# Gyroscope.net
KiCad netlist of a schematic drawn in Altium Designer
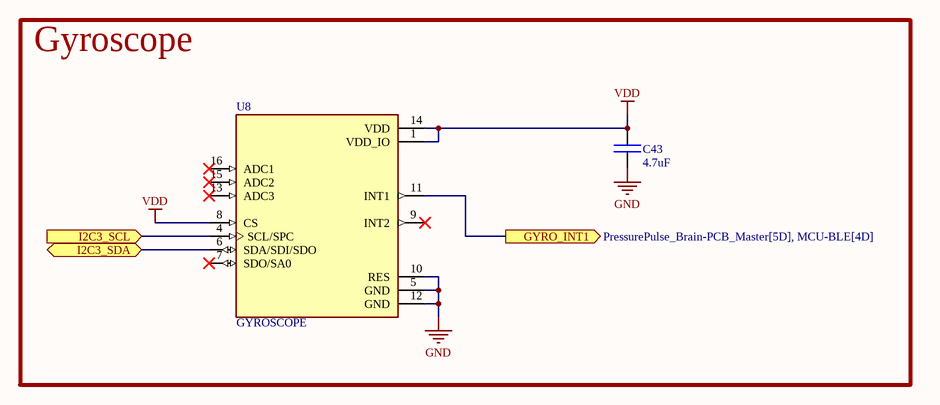
[diagram p0: Gyroscope.SchDoc]

(export (version "E")
  (design (tool "Eeschema 10.0.6"))
  (components
    (comp (ref "C43")
      (value "4.7uF")
      (footprint "PressurePulse:0402C")
      (description "Capacitor")
      (fields (field (name "Comment") "CAP"))
      (libsource (lib "PressurePulse") (part "CAP"))
    )
    (comp (ref "U8")
      (value "GYROSCOPE")
      (footprint "PressurePulse:16-VFLGA")
      (description "Accelerometer X, Y, Z Axis Â±2g, 4g, 8g, 16g 0.5Hz ~ 625Hz 16-LGA (3x3)")
      (fields (field (name "MFR") "STMicroelectronics"))
      (libsource (lib "PressurePulse") (part "GYROSCOPE"))
    )
  )
  (nets
    (net (code "1") (name "/GYRO_INT1") (class "Default")
      (node (ref "U8") (pin "11") (pinfunction "INT1_11") (pintype "output"))
    )
    (net (code "2") (name "/I2C3_SCL") (class "Default")
      (node (ref "U8") (pin "4") (pinfunction "SCL/SPC_4") (pintype "input"))
    )
    (net (code "3") (name "/I2C3_SDA") (class "Default")
      (node (ref "U8") (pin "6") (pinfunction "SDA/SDI/SDO_6") (pintype "bidirectional"))
    )
    (net (code "4") (name "GND") (class "Default")
      (node (ref "C43") (pin "1") (pinfunction "1_1") (pintype "passive"))
      (node (ref "U8") (pin "10") (pinfunction "RES_10") (pintype "passive"))
      (node (ref "U8") (pin "12") (pinfunction "GND_12") (pintype "power_in"))
      (node (ref "U8") (pin "5") (pinfunction "GND_5") (pintype "power_in"))
    )
    (net (code "5") (name "VDD") (class "Default")
      (node (ref "C43") (pin "2") (pinfunction "2_2") (pintype "passive"))
      (node (ref "U8") (pin "1") (pinfunction "VDD_IO_1") (pintype "power_in"))
      (node (ref "U8") (pin "14") (pinfunction "VDD_14") (pintype "power_in"))
      (node (ref "U8") (pin "8") (pinfunction "CS_8") (pintype "input"))
    )
    (net (code "6") (name "unconnected-(U8-ADC1-Pad16)") (class "Default")
      (node (ref "U8") (pin "16") (pinfunction "ADC1_16") (pintype "input+no_connect"))
    )
    (net (code "7") (name "unconnected-(U8-ADC2-Pad15)") (class "Default")
      (node (ref "U8") (pin "15") (pinfunction "ADC2_15") (pintype "input+no_connect"))
    )
    (net (code "8") (name "unconnected-(U8-ADC3-Pad13)") (class "Default")
      (node (ref "U8") (pin "13") (pinfunction "ADC3_13") (pintype "input+no_connect"))
    )
    (net (code "9") (name "unconnected-(U8-INT2-Pad9)") (class "Default")
      (node (ref "U8") (pin "9") (pinfunction "INT2_9") (pintype "output+no_connect"))
    )
    (net (code "10") (name "unconnected-(U8-SDO{slash}SA0-Pad7)") (class "Default")
      (node (ref "U8") (pin "7") (pinfunction "SDO/SA0_7") (pintype "bidirectional+no_connect"))
    )
  )
)
